# SilentStepStick-TMC2208_v10.net
KiCad netlist of a schematic drawn in EAGLE
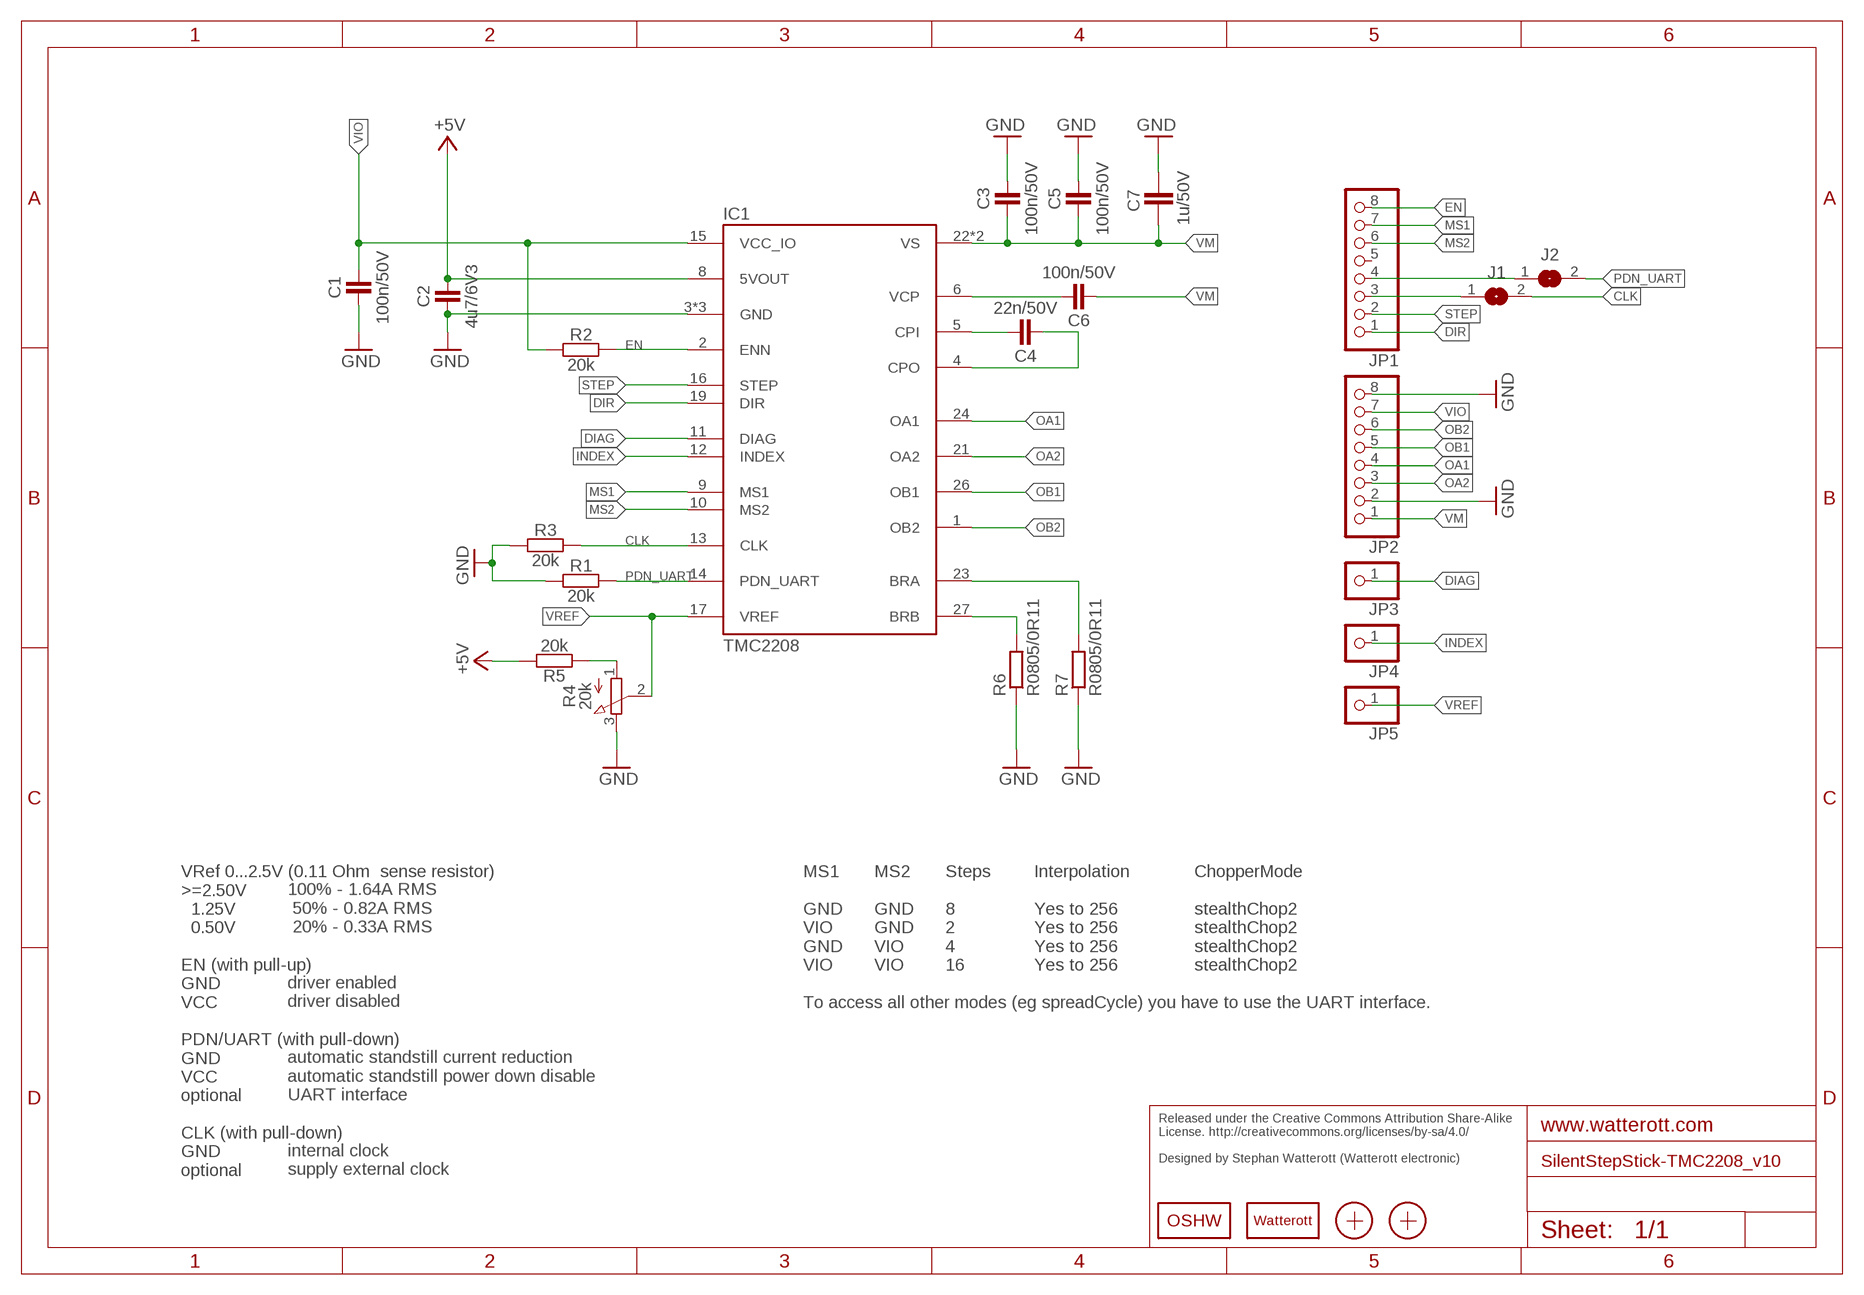
[diagram p0: schematic, sheet 1]

(export (version "E")
  (design (tool "Eeschema 10.0.6"))
  (components
    (comp (ref "C1")
      (value "100n/50V")
      (footprint "eagle-import:C0402")
      (libsource (lib "eagle-import") (part "CAPACITOR-0402"))
    )
    (comp (ref "C2")
      (value "4u7/6V3")
      (footprint "eagle-import:C0402")
      (libsource (lib "eagle-import") (part "CAPACITOR-0402"))
    )
    (comp (ref "C3")
      (value "100n/50V")
      (footprint "eagle-import:C0402")
      (libsource (lib "eagle-import") (part "CAPACITOR-0402"))
    )
    (comp (ref "C4")
      (value "22n/50V")
      (footprint "eagle-import:C0402")
      (libsource (lib "eagle-import") (part "CAPACITOR-0402"))
    )
    (comp (ref "C5")
      (value "100n/50V")
      (footprint "eagle-import:C0402")
      (libsource (lib "eagle-import") (part "CAPACITOR-0402"))
    )
    (comp (ref "C6")
      (value "100n/50V")
      (footprint "eagle-import:C0402")
      (libsource (lib "eagle-import") (part "CAPACITOR-0402"))
    )
    (comp (ref "C7")
      (value "1u/50V")
      (footprint "eagle-import:C0805")
      (libsource (lib "eagle-import") (part "C-EUC0805"))
    )
    (comp (ref "IC1")
      (value "TMC2208")
      (footprint "eagle-import:QFN28-PAD")
      (libsource (lib "eagle-import") (part "TMC2208"))
    )
    (comp (ref "J1")
      (value "JUMPER2-0402")
      (footprint "eagle-import:JUMPER2-0402")
      (libsource (lib "eagle-import") (part "JUMPER2-0402"))
    )
    (comp (ref "J2")
      (value "JUMPER2-0402")
      (footprint "eagle-import:JUMPER2-0402")
      (libsource (lib "eagle-import") (part "JUMPER2-0402"))
    )
    (comp (ref "JP1")
      (value "PINHD-1X08_2.54-S")
      (footprint "eagle-import:1X08-S")
      (libsource (lib "eagle-import") (part "PINHD-1X08_2.54-S"))
    )
    (comp (ref "JP2")
      (value "PINHD-1X08_2.54-S")
      (footprint "eagle-import:1X08-S")
      (libsource (lib "eagle-import") (part "PINHD-1X08_2.54-S"))
    )
    (comp (ref "JP3")
      (value "PINHD-1X1")
      (footprint "eagle-import:1X01")
      (libsource (lib "eagle-import") (part "PINHD-1X1"))
    )
    (comp (ref "JP4")
      (value "PINHD-1X1")
      (footprint "eagle-import:1X01")
      (libsource (lib "eagle-import") (part "PINHD-1X1"))
    )
    (comp (ref "JP5")
      (value "PINHD-1X1")
      (footprint "eagle-import:1X01")
      (libsource (lib "eagle-import") (part "PINHD-1X1"))
    )
    (comp (ref "LOGO1")
      (value "OSHW_LOGOX0070")
      (footprint "eagle-import:OSHW_6X70")
      (libsource (lib "eagle-import") (part "OSHW_LOGOX0070"))
    )
    (comp (ref "LOGO2")
      (value "LOGO-S_PLACE_M")
      (footprint "eagle-import:SPARK_TPLACE_M")
      (libsource (lib "eagle-import") (part "LOGO-S_PLACE_M"))
    )
    (comp (ref "R1")
      (value "20k")
      (footprint "eagle-import:C0402")
      (libsource (lib "eagle-import") (part "RESISTOR-0402"))
    )
    (comp (ref "R2")
      (value "20k")
      (footprint "eagle-import:C0402")
      (libsource (lib "eagle-import") (part "RESISTOR-0402"))
    )
    (comp (ref "R3")
      (value "20k")
      (footprint "eagle-import:C0402")
      (libsource (lib "eagle-import") (part "RESISTOR-0402"))
    )
    (comp (ref "R4")
      (value "20k")
      (footprint "eagle-import:POT_EVM3R")
      (libsource (lib "eagle-import") (part "POTEVM3R"))
    )
    (comp (ref "R5")
      (value "20k")
      (footprint "eagle-import:C0402")
      (libsource (lib "eagle-import") (part "RESISTOR-0402"))
    )
    (comp (ref "R6")
      (value "R0805/0R11")
      (footprint "eagle-import:M0805")
      (libsource (lib "eagle-import") (part "R-EU_M0805"))
    )
    (comp (ref "R7")
      (value "R0805/0R11")
      (footprint "eagle-import:M0805")
      (libsource (lib "eagle-import") (part "R-EU_M0805"))
    )
    (comp (ref "X1")
      (value "PASSER-04")
      (footprint "eagle-import:PASSER_04MM")
      (libsource (lib "eagle-import") (part "PASSER-04"))
    )
    (comp (ref "X2")
      (value "PASSER-04")
      (footprint "eagle-import:PASSER_04MM")
      (libsource (lib "eagle-import") (part "PASSER-04"))
    )
  )
  (nets
    (net (code "1") (name "+5V") (class "Default")
      (node (ref "C2") (pin "2") (pinfunction "2_2") (pintype "passive"))
      (node (ref "IC1") (pin "8") (pinfunction "5VOUT_8") (pintype "power_in"))
      (node (ref "R5") (pin "2") (pinfunction "2_2") (pintype "passive"))
    )
    (net (code "2") (name "CLK") (class "Default")
      (node (ref "IC1") (pin "13") (pinfunction "CLK_13") (pintype "bidirectional"))
      (node (ref "J1") (pin "2") (pinfunction "2_2") (pintype "passive"))
      (node (ref "R3") (pin "2") (pinfunction "2_2") (pintype "passive"))
    )
    (net (code "3") (name "DIAG") (class "Default")
      (node (ref "IC1") (pin "11") (pinfunction "DIAG_11") (pintype "bidirectional"))
      (node (ref "JP3") (pin "1") (pinfunction "1_1") (pintype "passive"))
    )
    (net (code "4") (name "DIR") (class "Default")
      (node (ref "IC1") (pin "19") (pinfunction "DIR_19") (pintype "bidirectional"))
      (node (ref "JP1") (pin "1") (pinfunction "1_1") (pintype "passive"))
    )
    (net (code "5") (name "EN") (class "Default")
      (node (ref "IC1") (pin "2") (pinfunction "ENN_2") (pintype "bidirectional"))
      (node (ref "JP1") (pin "8") (pinfunction "8_8") (pintype "passive"))
      (node (ref "R2") (pin "2") (pinfunction "2_2") (pintype "passive"))
    )
    (net (code "6") (name "GND") (class "Default")
      (node (ref "C1") (pin "1") (pinfunction "1_1") (pintype "passive"))
      (node (ref "C2") (pin "1") (pinfunction "1_1") (pintype "passive"))
      (node (ref "C3") (pin "2") (pinfunction "2_2") (pintype "passive"))
      (node (ref "C5") (pin "2") (pinfunction "2_2") (pintype "passive"))
      (node (ref "C7") (pin "2") (pinfunction "2_2") (pintype "passive"))
      (node (ref "IC1") (pin "18") (pinfunction "GND_18") (pintype "power_in"))
      (node (ref "IC1") (pin "3") (pinfunction "GND_3") (pintype "power_in"))
      (node (ref "IC1") (pin "TP") (pinfunction "GND_TP") (pintype "power_in"))
      (node (ref "JP2") (pin "2") (pinfunction "2_2") (pintype "passive"))
      (node (ref "JP2") (pin "8") (pinfunction "8_8") (pintype "passive"))
      (node (ref "R1") (pin "1") (pinfunction "1_1") (pintype "passive"))
      (node (ref "R3") (pin "1") (pinfunction "1_1") (pintype "passive"))
      (node (ref "R4") (pin "3") (pinfunction "E_3") (pintype "passive"))
      (node (ref "R6") (pin "1") (pinfunction "1_1") (pintype "passive"))
      (node (ref "R7") (pin "1") (pinfunction "1_1") (pintype "passive"))
    )
    (net (code "7") (name "INDEX") (class "Default")
      (node (ref "IC1") (pin "12") (pinfunction "INDEX_12") (pintype "bidirectional"))
      (node (ref "JP4") (pin "1") (pinfunction "1_1") (pintype "passive"))
    )
    (net (code "8") (name "MS1") (class "Default")
      (node (ref "IC1") (pin "9") (pinfunction "MS1_9") (pintype "bidirectional"))
      (node (ref "JP1") (pin "7") (pinfunction "7_7") (pintype "passive"))
    )
    (net (code "9") (name "MS2") (class "Default")
      (node (ref "IC1") (pin "10") (pinfunction "MS2_10") (pintype "bidirectional"))
      (node (ref "JP1") (pin "6") (pinfunction "6_6") (pintype "passive"))
    )
    (net (code "10") (name "Net-(IC1-BRA)") (class "Default")
      (node (ref "IC1") (pin "23") (pinfunction "BRA_23") (pintype "output"))
      (node (ref "R7") (pin "2") (pinfunction "2_2") (pintype "passive"))
    )
    (net (code "11") (name "Net-(IC1-BRB)") (class "Default")
      (node (ref "IC1") (pin "27") (pinfunction "BRB_27") (pintype "output"))
      (node (ref "R6") (pin "2") (pinfunction "2_2") (pintype "passive"))
    )
    (net (code "12") (name "Net-(IC1-CPI)") (class "Default")
      (node (ref "C4") (pin "2") (pinfunction "2_2") (pintype "passive"))
      (node (ref "IC1") (pin "5") (pinfunction "CPI_5") (pintype "passive"))
    )
    (net (code "13") (name "Net-(IC1-CPO)") (class "Default")
      (node (ref "C4") (pin "1") (pinfunction "1_1") (pintype "passive"))
      (node (ref "IC1") (pin "4") (pinfunction "CPO_4") (pintype "passive"))
    )
    (net (code "14") (name "Net-(IC1-VCP)") (class "Default")
      (node (ref "C6") (pin "2") (pinfunction "2_2") (pintype "passive"))
      (node (ref "IC1") (pin "6") (pinfunction "VCP_6") (pintype "passive"))
    )
    (net (code "15") (name "Net-(J1-Pad1)") (class "Default")
      (node (ref "J1") (pin "1") (pinfunction "1_1") (pintype "passive"))
      (node (ref "JP1") (pin "3") (pinfunction "3_3") (pintype "passive"))
    )
    (net (code "16") (name "Net-(J2-Pad1)") (class "Default")
      (node (ref "J2") (pin "1") (pinfunction "1_1") (pintype "passive"))
      (node (ref "JP1") (pin "4") (pinfunction "4_4") (pintype "passive"))
    )
    (net (code "17") (name "Net-(R4-A)") (class "Default")
      (node (ref "R4") (pin "1") (pinfunction "A_1") (pintype "passive"))
      (node (ref "R5") (pin "1") (pinfunction "1_1") (pintype "passive"))
    )
    (net (code "18") (name "OA1") (class "Default")
      (node (ref "IC1") (pin "24") (pinfunction "OA1_24") (pintype "output"))
      (node (ref "JP2") (pin "4") (pinfunction "4_4") (pintype "passive"))
    )
    (net (code "19") (name "OA2") (class "Default")
      (node (ref "IC1") (pin "21") (pinfunction "OA2_21") (pintype "output"))
      (node (ref "JP2") (pin "3") (pinfunction "3_3") (pintype "passive"))
    )
    (net (code "20") (name "OB1") (class "Default")
      (node (ref "IC1") (pin "26") (pinfunction "OB1_26") (pintype "output"))
      (node (ref "JP2") (pin "5") (pinfunction "5_5") (pintype "passive"))
    )
    (net (code "21") (name "OB2") (class "Default")
      (node (ref "IC1") (pin "1") (pinfunction "OB2_1") (pintype "output"))
      (node (ref "JP2") (pin "6") (pinfunction "6_6") (pintype "passive"))
    )
    (net (code "22") (name "PDN_UART") (class "Default")
      (node (ref "IC1") (pin "14") (pinfunction "PDN_UART_14") (pintype "bidirectional"))
      (node (ref "J2") (pin "2") (pinfunction "2_2") (pintype "passive"))
      (node (ref "R1") (pin "2") (pinfunction "2_2") (pintype "passive"))
    )
    (net (code "23") (name "STEP") (class "Default")
      (node (ref "IC1") (pin "16") (pinfunction "STEP_16") (pintype "bidirectional"))
      (node (ref "JP1") (pin "2") (pinfunction "2_2") (pintype "passive"))
    )
    (net (code "24") (name "VIO") (class "Default")
      (node (ref "C1") (pin "2") (pinfunction "2_2") (pintype "passive"))
      (node (ref "IC1") (pin "15") (pinfunction "VCC_IO_15") (pintype "power_in"))
      (node (ref "JP2") (pin "7") (pinfunction "7_7") (pintype "passive"))
      (node (ref "R2") (pin "1") (pinfunction "1_1") (pintype "passive"))
    )
    (net (code "25") (name "VM") (class "Default")
      (node (ref "C3") (pin "1") (pinfunction "1_1") (pintype "passive"))
      (node (ref "C5") (pin "1") (pinfunction "1_1") (pintype "passive"))
      (node (ref "C6") (pin "1") (pinfunction "1_1") (pintype "passive"))
      (node (ref "C7") (pin "1") (pinfunction "1_1") (pintype "passive"))
      (node (ref "IC1") (pin "22") (pinfunction "VS_22") (pintype "power_in"))
      (node (ref "IC1") (pin "28") (pinfunction "VS_28") (pintype "power_in"))
      (node (ref "JP2") (pin "1") (pinfunction "1_1") (pintype "passive"))
    )
    (net (code "26") (name "VREF") (class "Default")
      (node (ref "IC1") (pin "17") (pinfunction "VREF_17") (pintype "passive"))
      (node (ref "JP5") (pin "1") (pinfunction "1_1") (pintype "passive"))
      (node (ref "R4") (pin "2") (pinfunction "S_2") (pintype "passive"))
    )
    (net (code "27") (name "unconnected-(JP1-Pad5)") (class "Default")
      (node (ref "JP1") (pin "5") (pinfunction "5_5") (pintype "passive"))
    )
  )
)
